# 2-50Pin_B2B_Connector.net
KiCad netlist of a schematic drawn in Altium Designer
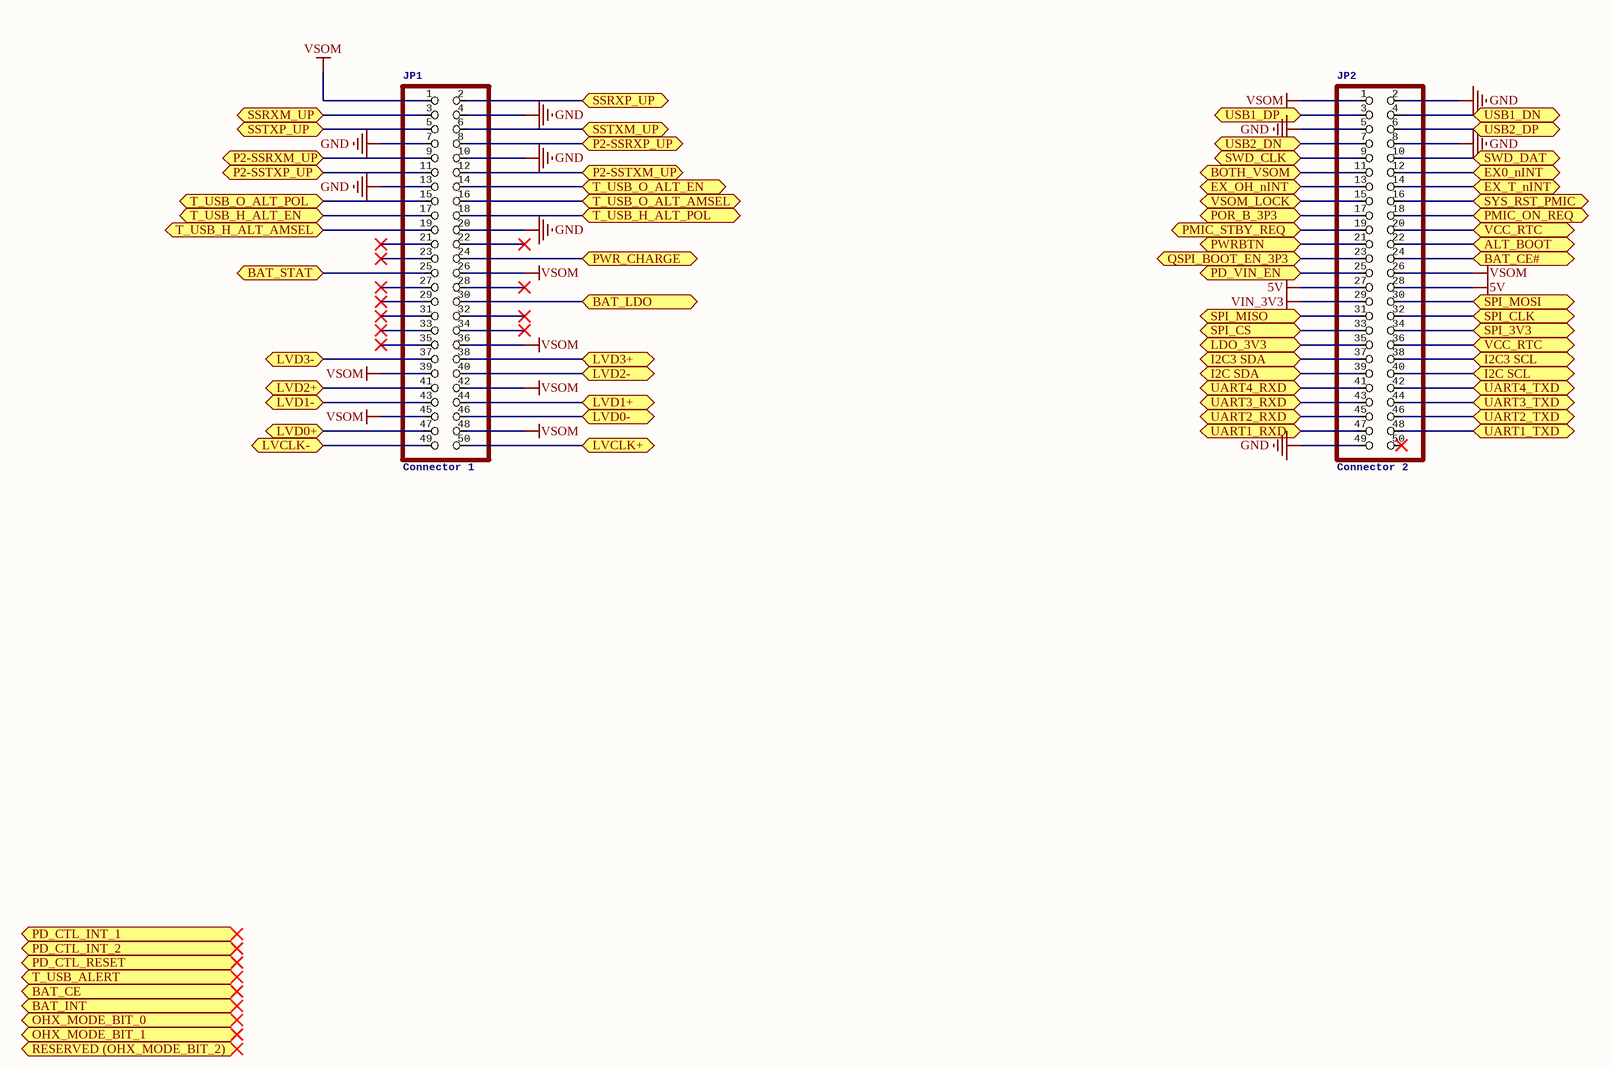
[diagram p0: 2-50Pin B2B Connector.SchDoc]

(export (version "E")
  (design (tool "Eeschema 10.0.6"))
  (components
    (comp (ref "JP1")
      (value "Connector 1")
      (footprint "2X25")
      (libsource (lib "pinhead") (part "PINHD-2X25"))
    )
    (comp (ref "JP2")
      (value "Connector 2")
      (footprint "2X25")
      (libsource (lib "pinhead") (part "PINHD-2X25"))
    )
  )
  (nets
    (net (code "1") (name "/ALT_BOOT") (class "Default")
      (node (ref "JP2") (pin "22") (pinfunction "22_22") (pintype "passive"))
    )
    (net (code "3") (name "/BAT_CE#") (class "Default")
      (node (ref "JP2") (pin "24") (pinfunction "24_24") (pintype "passive"))
    )
    (net (code "5") (name "/BAT_LDO") (class "Default")
      (node (ref "JP1") (pin "30") (pinfunction "30_30") (pintype "passive"))
    )
    (net (code "6") (name "/BAT_STAT") (class "Default")
      (node (ref "JP1") (pin "25") (pinfunction "25_25") (pintype "passive"))
    )
    (net (code "7") (name "/BOTH_VSOM") (class "Default")
      (node (ref "JP2") (pin "11") (pinfunction "11_11") (pintype "passive"))
    )
    (net (code "8") (name "/EX0_nINT") (class "Default")
      (node (ref "JP2") (pin "12") (pinfunction "12_12") (pintype "passive"))
    )
    (net (code "9") (name "/EX_OH_nINT") (class "Default")
      (node (ref "JP2") (pin "13") (pinfunction "13_13") (pintype "passive"))
    )
    (net (code "10") (name "/EX_T_nINT") (class "Default")
      (node (ref "JP2") (pin "14") (pinfunction "14_14") (pintype "passive"))
    )
    (net (code "11") (name "/I2C SCL") (class "Default")
      (node (ref "JP2") (pin "40") (pinfunction "40_40") (pintype "passive"))
    )
    (net (code "12") (name "/I2C SDA") (class "Default")
      (node (ref "JP2") (pin "39") (pinfunction "39_39") (pintype "passive"))
    )
    (net (code "13") (name "/I2C3 SCL") (class "Default")
      (node (ref "JP2") (pin "38") (pinfunction "38_38") (pintype "passive"))
    )
    (net (code "14") (name "/I2C3 SDA") (class "Default")
      (node (ref "JP2") (pin "37") (pinfunction "37_37") (pintype "passive"))
    )
    (net (code "15") (name "/LDO_3V3") (class "Default")
      (node (ref "JP2") (pin "35") (pinfunction "35_35") (pintype "passive"))
    )
    (net (code "16") (name "/LVCLK+") (class "Default")
      (node (ref "JP1") (pin "50") (pinfunction "50_50") (pintype "passive"))
    )
    (net (code "17") (name "/LVCLK-") (class "Default")
      (node (ref "JP1") (pin "49") (pinfunction "49_49") (pintype "passive"))
    )
    (net (code "18") (name "/LVD0+") (class "Default")
      (node (ref "JP1") (pin "47") (pinfunction "47_47") (pintype "passive"))
    )
    (net (code "19") (name "/LVD0-") (class "Default")
      (node (ref "JP1") (pin "46") (pinfunction "46_46") (pintype "passive"))
    )
    (net (code "20") (name "/LVD1+") (class "Default")
      (node (ref "JP1") (pin "44") (pinfunction "44_44") (pintype "passive"))
    )
    (net (code "21") (name "/LVD1-") (class "Default")
      (node (ref "JP1") (pin "43") (pinfunction "43_43") (pintype "passive"))
    )
    (net (code "22") (name "/LVD2+") (class "Default")
      (node (ref "JP1") (pin "41") (pinfunction "41_41") (pintype "passive"))
    )
    (net (code "23") (name "/LVD2-") (class "Default")
      (node (ref "JP1") (pin "40") (pinfunction "40_40") (pintype "passive"))
    )
    (net (code "24") (name "/LVD3+") (class "Default")
      (node (ref "JP1") (pin "38") (pinfunction "38_38") (pintype "passive"))
    )
    (net (code "25") (name "/LVD3-") (class "Default")
      (node (ref "JP1") (pin "37") (pinfunction "37_37") (pintype "passive"))
    )
    (net (code "28") (name "/P2-SSRXM_UP") (class "Default")
      (node (ref "JP1") (pin "9") (pinfunction "9_9") (pintype "passive"))
    )
    (net (code "29") (name "/P2-SSRXP_UP") (class "Default")
      (node (ref "JP1") (pin "8") (pinfunction "8_8") (pintype "passive"))
    )
    (net (code "30") (name "/P2-SSTXM_UP") (class "Default")
      (node (ref "JP1") (pin "12") (pinfunction "12_12") (pintype "passive"))
    )
    (net (code "31") (name "/P2-SSTXP_UP") (class "Default")
      (node (ref "JP1") (pin "11") (pinfunction "11_11") (pintype "passive"))
    )
    (net (code "35") (name "/PD_VIN_EN") (class "Default")
      (node (ref "JP2") (pin "25") (pinfunction "25_25") (pintype "passive"))
    )
    (net (code "36") (name "/PMIC_ON_REQ") (class "Default")
      (node (ref "JP2") (pin "18") (pinfunction "18_18") (pintype "passive"))
    )
    (net (code "37") (name "/PMIC_STBY_REQ") (class "Default")
      (node (ref "JP2") (pin "19") (pinfunction "19_19") (pintype "passive"))
    )
    (net (code "38") (name "/POR_B_3P3") (class "Default")
      (node (ref "JP2") (pin "17") (pinfunction "17_17") (pintype "passive"))
    )
    (net (code "39") (name "/PWRBTN") (class "Default")
      (node (ref "JP2") (pin "21") (pinfunction "21_21") (pintype "passive"))
    )
    (net (code "40") (name "/PWR_CHARGE") (class "Default")
      (node (ref "JP1") (pin "24") (pinfunction "24_24") (pintype "passive"))
    )
    (net (code "41") (name "/QSPI_BOOT_EN_3P3") (class "Default")
      (node (ref "JP2") (pin "23") (pinfunction "23_23") (pintype "passive"))
    )
    (net (code "43") (name "/SPI_3V3") (class "Default")
      (node (ref "JP2") (pin "34") (pinfunction "34_34") (pintype "passive"))
    )
    (net (code "44") (name "/SPI_CLK") (class "Default")
      (node (ref "JP2") (pin "32") (pinfunction "32_32") (pintype "passive"))
    )
    (net (code "45") (name "/SPI_CS") (class "Default")
      (node (ref "JP2") (pin "33") (pinfunction "33_33") (pintype "passive"))
    )
    (net (code "46") (name "/SPI_MISO") (class "Default")
      (node (ref "JP2") (pin "31") (pinfunction "31_31") (pintype "passive"))
    )
    (net (code "47") (name "/SPI_MOSI") (class "Default")
      (node (ref "JP2") (pin "30") (pinfunction "30_30") (pintype "passive"))
    )
    (net (code "48") (name "/SSRXM_UP") (class "Default")
      (node (ref "JP1") (pin "3") (pinfunction "3_3") (pintype "passive"))
    )
    (net (code "49") (name "/SSRXP_UP") (class "Default")
      (node (ref "JP1") (pin "2") (pinfunction "2_2") (pintype "passive"))
    )
    (net (code "50") (name "/SSTXM_UP") (class "Default")
      (node (ref "JP1") (pin "6") (pinfunction "6_6") (pintype "passive"))
    )
    (net (code "51") (name "/SSTXP_UP") (class "Default")
      (node (ref "JP1") (pin "5") (pinfunction "5_5") (pintype "passive"))
    )
    (net (code "52") (name "/SWD_CLK") (class "Default")
      (node (ref "JP2") (pin "9") (pinfunction "9_9") (pintype "passive"))
    )
    (net (code "53") (name "/SWD_DAT") (class "Default")
      (node (ref "JP2") (pin "10") (pinfunction "10_10") (pintype "passive"))
    )
    (net (code "54") (name "/SYS_RST_PMIC") (class "Default")
      (node (ref "JP2") (pin "16") (pinfunction "16_16") (pintype "passive"))
    )
    (net (code "56") (name "/T_USB_H_ALT_AMSEL") (class "Default")
      (node (ref "JP1") (pin "19") (pinfunction "19_19") (pintype "passive"))
    )
    (net (code "57") (name "/T_USB_H_ALT_EN") (class "Default")
      (node (ref "JP1") (pin "17") (pinfunction "17_17") (pintype "passive"))
    )
    (net (code "58") (name "/T_USB_H_ALT_POL") (class "Default")
      (node (ref "JP1") (pin "18") (pinfunction "18_18") (pintype "passive"))
    )
    (net (code "59") (name "/T_USB_O_ALT_AMSEL") (class "Default")
      (node (ref "JP1") (pin "16") (pinfunction "16_16") (pintype "passive"))
    )
    (net (code "60") (name "/T_USB_O_ALT_EN") (class "Default")
      (node (ref "JP1") (pin "14") (pinfunction "14_14") (pintype "passive"))
    )
    (net (code "61") (name "/T_USB_O_ALT_POL") (class "Default")
      (node (ref "JP1") (pin "15") (pinfunction "15_15") (pintype "passive"))
    )
    (net (code "62") (name "/UART1_RXD") (class "Default")
      (node (ref "JP2") (pin "47") (pinfunction "47_47") (pintype "passive"))
    )
    (net (code "63") (name "/UART1_TXD") (class "Default")
      (node (ref "JP2") (pin "48") (pinfunction "48_48") (pintype "passive"))
    )
    (net (code "64") (name "/UART2_RXD") (class "Default")
      (node (ref "JP2") (pin "45") (pinfunction "45_45") (pintype "passive"))
    )
    (net (code "65") (name "/UART2_TXD") (class "Default")
      (node (ref "JP2") (pin "46") (pinfunction "46_46") (pintype "passive"))
    )
    (net (code "66") (name "/UART3_RXD") (class "Default")
      (node (ref "JP2") (pin "43") (pinfunction "43_43") (pintype "passive"))
    )
    (net (code "67") (name "/UART3_TXD") (class "Default")
      (node (ref "JP2") (pin "44") (pinfunction "44_44") (pintype "passive"))
    )
    (net (code "68") (name "/UART4_RXD") (class "Default")
      (node (ref "JP2") (pin "41") (pinfunction "41_41") (pintype "passive"))
    )
    (net (code "69") (name "/UART4_TXD") (class "Default")
      (node (ref "JP2") (pin "42") (pinfunction "42_42") (pintype "passive"))
    )
    (net (code "70") (name "/USB1_DN") (class "Default")
      (node (ref "JP2") (pin "4") (pinfunction "4_4") (pintype "passive"))
    )
    (net (code "71") (name "/USB1_DP") (class "Default")
      (node (ref "JP2") (pin "3") (pinfunction "3_3") (pintype "passive"))
    )
    (net (code "72") (name "/USB2_DN") (class "Default")
      (node (ref "JP2") (pin "7") (pinfunction "7_7") (pintype "passive"))
    )
    (net (code "73") (name "/USB2_DP") (class "Default")
      (node (ref "JP2") (pin "6") (pinfunction "6_6") (pintype "passive"))
    )
    (net (code "74") (name "/VCC_RTC") (class "Default")
      (node (ref "JP2") (pin "20") (pinfunction "20_20") (pintype "passive"))
      (node (ref "JP2") (pin "36") (pinfunction "36_36") (pintype "passive"))
    )
    (net (code "75") (name "/VSOM_LOCK") (class "Default")
      (node (ref "JP2") (pin "15") (pinfunction "15_15") (pintype "passive"))
    )
    (net (code "76") (name "5V") (class "Default")
      (node (ref "JP2") (pin "27") (pinfunction "27_27") (pintype "passive"))
      (node (ref "JP2") (pin "28") (pinfunction "28_28") (pintype "passive"))
    )
    (net (code "77") (name "GND") (class "Default")
      (node (ref "JP1") (pin "10") (pinfunction "10_10") (pintype "passive"))
      (node (ref "JP1") (pin "13") (pinfunction "13_13") (pintype "passive"))
      (node (ref "JP1") (pin "20") (pinfunction "20_20") (pintype "passive"))
      (node (ref "JP1") (pin "4") (pinfunction "4_4") (pintype "passive"))
      (node (ref "JP1") (pin "7") (pinfunction "7_7") (pintype "passive"))
      (node (ref "JP2") (pin "2") (pinfunction "2_2") (pintype "passive"))
      (node (ref "JP2") (pin "49") (pinfunction "49_49") (pintype "passive"))
      (node (ref "JP2") (pin "5") (pinfunction "5_5") (pintype "passive"))
      (node (ref "JP2") (pin "8") (pinfunction "8_8") (pintype "passive"))
    )
    (net (code "78") (name "VIN_3V3") (class "Default")
      (node (ref "JP2") (pin "29") (pinfunction "29_29") (pintype "passive"))
    )
    (net (code "79") (name "VSOM") (class "Default")
      (node (ref "JP1") (pin "1") (pinfunction "1_1") (pintype "passive"))
      (node (ref "JP1") (pin "26") (pinfunction "26_26") (pintype "passive"))
      (node (ref "JP1") (pin "36") (pinfunction "36_36") (pintype "passive"))
      (node (ref "JP1") (pin "39") (pinfunction "39_39") (pintype "passive"))
      (node (ref "JP1") (pin "42") (pinfunction "42_42") (pintype "passive"))
      (node (ref "JP1") (pin "45") (pinfunction "45_45") (pintype "passive"))
      (node (ref "JP1") (pin "48") (pinfunction "48_48") (pintype "passive"))
      (node (ref "JP2") (pin "1") (pinfunction "1_1") (pintype "passive"))
      (node (ref "JP2") (pin "26") (pinfunction "26_26") (pintype "passive"))
    )
    (net (code "80") (name "unconnected-(JP1-Pad21)") (class "Default")
      (node (ref "JP1") (pin "21") (pinfunction "21_21") (pintype "passive+no_connect"))
    )
    (net (code "81") (name "unconnected-(JP1-Pad22)") (class "Default")
      (node (ref "JP1") (pin "22") (pinfunction "22_22") (pintype "passive+no_connect"))
    )
    (net (code "82") (name "unconnected-(JP1-Pad23)") (class "Default")
      (node (ref "JP1") (pin "23") (pinfunction "23_23") (pintype "passive+no_connect"))
    )
    (net (code "83") (name "unconnected-(JP1-Pad27)") (class "Default")
      (node (ref "JP1") (pin "27") (pinfunction "27_27") (pintype "passive+no_connect"))
    )
    (net (code "84") (name "unconnected-(JP1-Pad28)") (class "Default")
      (node (ref "JP1") (pin "28") (pinfunction "28_28") (pintype "passive+no_connect"))
    )
    (net (code "85") (name "unconnected-(JP1-Pad29)") (class "Default")
      (node (ref "JP1") (pin "29") (pinfunction "29_29") (pintype "passive+no_connect"))
    )
    (net (code "86") (name "unconnected-(JP1-Pad31)") (class "Default")
      (node (ref "JP1") (pin "31") (pinfunction "31_31") (pintype "passive+no_connect"))
    )
    (net (code "87") (name "unconnected-(JP1-Pad32)") (class "Default")
      (node (ref "JP1") (pin "32") (pinfunction "32_32") (pintype "passive+no_connect"))
    )
    (net (code "88") (name "unconnected-(JP1-Pad33)") (class "Default")
      (node (ref "JP1") (pin "33") (pinfunction "33_33") (pintype "passive+no_connect"))
    )
    (net (code "89") (name "unconnected-(JP1-Pad34)") (class "Default")
      (node (ref "JP1") (pin "34") (pinfunction "34_34") (pintype "passive+no_connect"))
    )
    (net (code "90") (name "unconnected-(JP1-Pad35)") (class "Default")
      (node (ref "JP1") (pin "35") (pinfunction "35_35") (pintype "passive+no_connect"))
    )
    (net (code "91") (name "unconnected-(JP2-Pad50)") (class "Default")
      (node (ref "JP2") (pin "50") (pinfunction "50_50") (pintype "passive+no_connect"))
    )
  )
)
